# MiniMixer.net
KiCad netlist of a schematic drawn in EAGLE
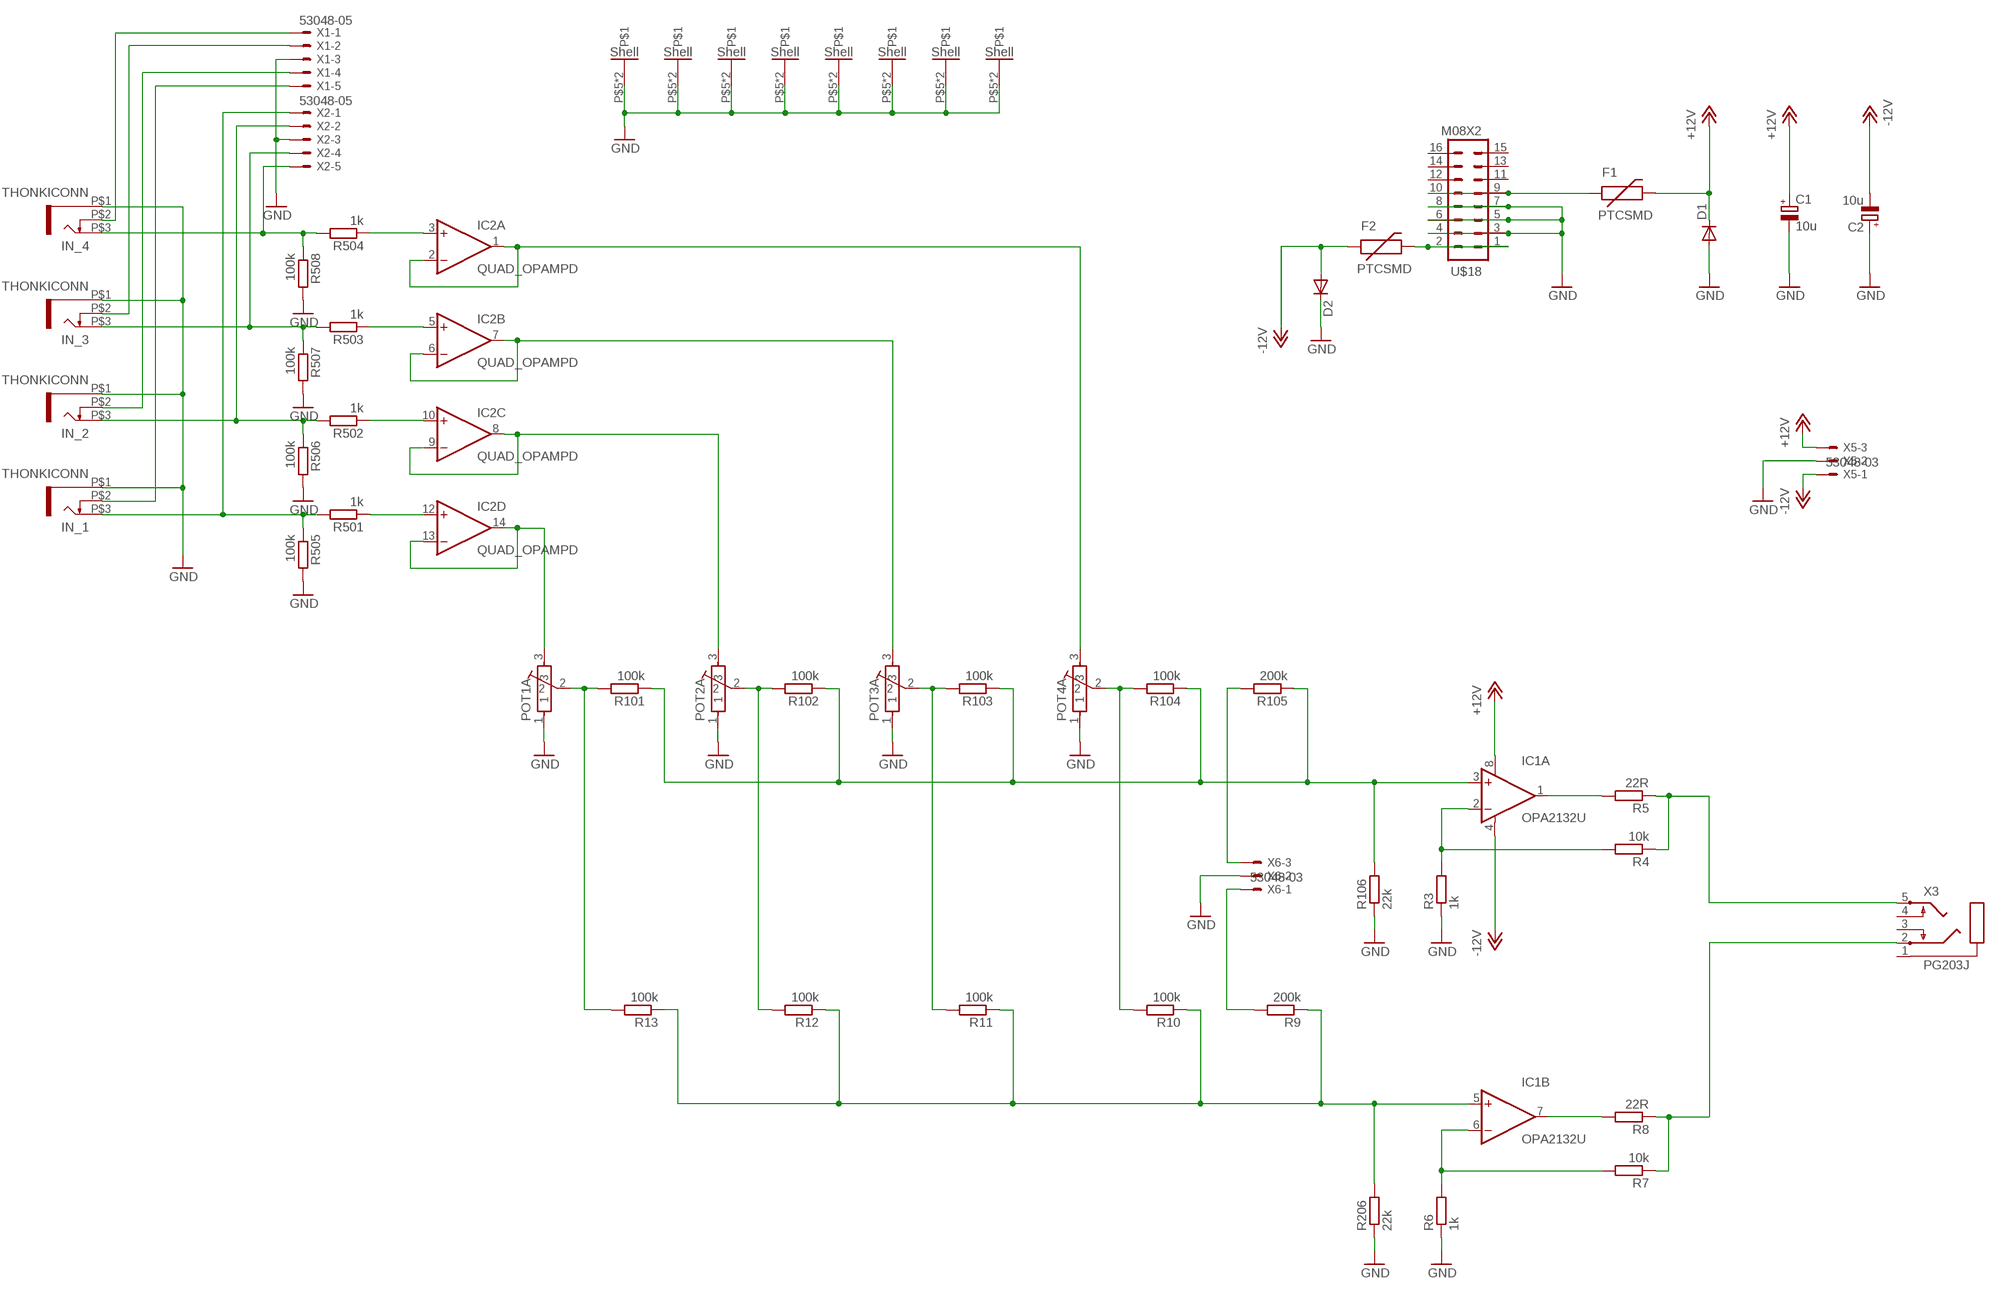
[diagram p0: schematic, sheet 1]

(export (version "E")
  (design (tool "Eeschema 10.0.6"))
  (components
    (comp (ref "C1")
      (value "10u")
      (footprint "eagle-import:153CLV-0505")
      (libsource (lib "eagle-import") (part "CPOL-EU153CLV-0505"))
    )
    (comp (ref "C2")
      (value "10u")
      (footprint "eagle-import:153CLV-0505")
      (libsource (lib "eagle-import") (part "CPOL-EU153CLV-0505"))
    )
    (comp (ref "D1")
      (value "DIODESMA")
      (footprint "eagle-import:SMA-DIODE")
      (libsource (lib "eagle-import") (part "DIODESMA"))
    )
    (comp (ref "D2")
      (value "DIODESMA")
      (footprint "eagle-import:SMA-DIODE")
      (libsource (lib "eagle-import") (part "DIODESMA"))
    )
    (comp (ref "F1")
      (value "PTCSMD")
      (footprint "eagle-import:PTC-1206")
      (libsource (lib "eagle-import") (part "PTCSMD"))
    )
    (comp (ref "F2")
      (value "PTCSMD")
      (footprint "eagle-import:PTC-1206")
      (libsource (lib "eagle-import") (part "PTCSMD"))
    )
    (comp (ref "IC1")
      (value "OPA2132U")
      (footprint "eagle-import:SO08")
      (fields (field (name "MF") "TEXAS INSTRUMENTS"))
      (libsource (lib "eagle-import") (part "OPA2132U"))
    )
    (comp (ref "IC2")
      (value "QUAD_OPAMPD")
      (footprint "eagle-import:SO14")
      (libsource (lib "eagle-import") (part "QUAD_OPAMPD"))
    )
    (comp (ref "IN_1")
      (value "THONKICONN")
      (footprint "eagle-import:THONKICONN")
      (libsource (lib "eagle-import") (part "THONKICONN"))
    )
    (comp (ref "IN_2")
      (value "THONKICONN")
      (footprint "eagle-import:THONKICONN")
      (libsource (lib "eagle-import") (part "THONKICONN"))
    )
    (comp (ref "IN_3")
      (value "THONKICONN")
      (footprint "eagle-import:THONKICONN")
      (libsource (lib "eagle-import") (part "THONKICONN"))
    )
    (comp (ref "IN_4")
      (value "THONKICONN")
      (footprint "eagle-import:THONKICONN")
      (libsource (lib "eagle-import") (part "THONKICONN"))
    )
    (comp (ref "POT1A")
      (value "POT-ALPS-RK09L1140")
      (footprint "eagle-import:POT-ALPS-RK09L1140")
      (libsource (lib "eagle-import") (part "POT-ALPS-RK09L1140"))
    )
    (comp (ref "POT1B")
      (value "POT-ALPS-RK09L1140")
      (footprint "eagle-import:POT-ALPS-RK09L1140")
      (libsource (lib "eagle-import") (part "POT-ALPS-RK09L1140"))
    )
    (comp (ref "POT2A")
      (value "POT-ALPS-RK09L1140")
      (footprint "eagle-import:POT-ALPS-RK09L1140")
      (libsource (lib "eagle-import") (part "POT-ALPS-RK09L1140"))
    )
    (comp (ref "POT2B")
      (value "POT-ALPS-RK09L1140")
      (footprint "eagle-import:POT-ALPS-RK09L1140")
      (libsource (lib "eagle-import") (part "POT-ALPS-RK09L1140"))
    )
    (comp (ref "POT3A")
      (value "POT-ALPS-RK09L1140")
      (footprint "eagle-import:POT-ALPS-RK09L1140")
      (libsource (lib "eagle-import") (part "POT-ALPS-RK09L1140"))
    )
    (comp (ref "POT3B")
      (value "POT-ALPS-RK09L1140")
      (footprint "eagle-import:POT-ALPS-RK09L1140")
      (libsource (lib "eagle-import") (part "POT-ALPS-RK09L1140"))
    )
    (comp (ref "POT4A")
      (value "POT-ALPS-RK09L1140")
      (footprint "eagle-import:POT-ALPS-RK09L1140")
      (libsource (lib "eagle-import") (part "POT-ALPS-RK09L1140"))
    )
    (comp (ref "POT4B")
      (value "POT-ALPS-RK09L1140")
      (footprint "eagle-import:POT-ALPS-RK09L1140")
      (libsource (lib "eagle-import") (part "POT-ALPS-RK09L1140"))
    )
    (comp (ref "R3")
      (value "1k")
      (footprint "eagle-import:0603")
      (libsource (lib "eagle-import") (part "R-EU_0603"))
    )
    (comp (ref "R4")
      (value "10k")
      (footprint "eagle-import:0603")
      (libsource (lib "eagle-import") (part "R-EU_0603"))
    )
    (comp (ref "R5")
      (value "22R")
      (footprint "eagle-import:0603")
      (libsource (lib "eagle-import") (part "R-EU_0603"))
    )
    (comp (ref "R6")
      (value "1k")
      (footprint "eagle-import:0603")
      (libsource (lib "eagle-import") (part "R-EU_0603"))
    )
    (comp (ref "R7")
      (value "10k")
      (footprint "eagle-import:0603")
      (libsource (lib "eagle-import") (part "R-EU_0603"))
    )
    (comp (ref "R8")
      (value "22R")
      (footprint "eagle-import:0603")
      (libsource (lib "eagle-import") (part "R-EU_0603"))
    )
    (comp (ref "R9")
      (value "200k")
      (footprint "eagle-import:R0603")
      (libsource (lib "eagle-import") (part "R-EU_R0603"))
    )
    (comp (ref "R10")
      (value "100k")
      (footprint "eagle-import:R0603")
      (libsource (lib "eagle-import") (part "R-EU_R0603"))
    )
    (comp (ref "R11")
      (value "100k")
      (footprint "eagle-import:R0603")
      (libsource (lib "eagle-import") (part "R-EU_R0603"))
    )
    (comp (ref "R12")
      (value "100k")
      (footprint "eagle-import:R0603")
      (libsource (lib "eagle-import") (part "R-EU_R0603"))
    )
    (comp (ref "R13")
      (value "100k")
      (footprint "eagle-import:R0603")
      (libsource (lib "eagle-import") (part "R-EU_R0603"))
    )
    (comp (ref "R101")
      (value "100k")
      (footprint "eagle-import:R0603")
      (libsource (lib "eagle-import") (part "R-EU_R0603"))
    )
    (comp (ref "R102")
      (value "100k")
      (footprint "eagle-import:R0603")
      (libsource (lib "eagle-import") (part "R-EU_R0603"))
    )
    (comp (ref "R103")
      (value "100k")
      (footprint "eagle-import:R0603")
      (libsource (lib "eagle-import") (part "R-EU_R0603"))
    )
    (comp (ref "R104")
      (value "100k")
      (footprint "eagle-import:R0603")
      (libsource (lib "eagle-import") (part "R-EU_R0603"))
    )
    (comp (ref "R105")
      (value "200k")
      (footprint "eagle-import:R0603")
      (libsource (lib "eagle-import") (part "R-EU_R0603"))
    )
    (comp (ref "R106")
      (value "22k")
      (footprint "eagle-import:0603")
      (libsource (lib "eagle-import") (part "R-EU_0603"))
    )
    (comp (ref "R206")
      (value "22k")
      (footprint "eagle-import:0603")
      (libsource (lib "eagle-import") (part "R-EU_0603"))
    )
    (comp (ref "R501")
      (value "1k")
      (footprint "eagle-import:R0603")
      (libsource (lib "eagle-import") (part "R-EU_R0603"))
    )
    (comp (ref "R502")
      (value "1k")
      (footprint "eagle-import:R0603")
      (libsource (lib "eagle-import") (part "R-EU_R0603"))
    )
    (comp (ref "R503")
      (value "1k")
      (footprint "eagle-import:R0603")
      (libsource (lib "eagle-import") (part "R-EU_R0603"))
    )
    (comp (ref "R504")
      (value "1k")
      (footprint "eagle-import:R0603")
      (libsource (lib "eagle-import") (part "R-EU_R0603"))
    )
    (comp (ref "R505")
      (value "100k")
      (footprint "eagle-import:R0603")
      (libsource (lib "eagle-import") (part "R-EU_R0603"))
    )
    (comp (ref "R506")
      (value "100k")
      (footprint "eagle-import:R0603")
      (libsource (lib "eagle-import") (part "R-EU_R0603"))
    )
    (comp (ref "R507")
      (value "100k")
      (footprint "eagle-import:R0603")
      (libsource (lib "eagle-import") (part "R-EU_R0603"))
    )
    (comp (ref "R508")
      (value "100k")
      (footprint "eagle-import:R0603")
      (libsource (lib "eagle-import") (part "R-EU_R0603"))
    )
    (comp (ref "U$18")
      (value "M08X2")
      (footprint "eagle-import:2X8")
      (libsource (lib "eagle-import") (part "M08X2"))
    )
    (comp (ref "X1")
      (value "53048-05")
      (footprint "eagle-import:53048-05")
      (fields (field (name "MF") "MOLEX") (field (name "MPN") "53048-0510"))
      (libsource (lib "eagle-import") (part "53?-05048"))
    )
    (comp (ref "X2")
      (value "53048-05")
      (footprint "eagle-import:53048-05")
      (fields (field (name "MF") "MOLEX") (field (name "MPN") "53048-0510"))
      (libsource (lib "eagle-import") (part "53?-05048"))
    )
    (comp (ref "X3")
      (value "PG203J")
      (footprint "eagle-import:PG203J")
      (libsource (lib "eagle-import") (part "PG203J"))
    )
    (comp (ref "X5")
      (value "53048-03")
      (footprint "eagle-import:53048-03")
      (fields (field (name "MF") "WALDOM/MOLEX") (field (name "MPN") "53048-0310"))
      (libsource (lib "eagle-import") (part "53?-03048"))
    )
    (comp (ref "X6")
      (value "53048-03")
      (footprint "eagle-import:53048-03")
      (fields (field (name "MF") "WALDOM/MOLEX") (field (name "MPN") "53048-0310"))
      (libsource (lib "eagle-import") (part "53?-03048"))
    )
  )
  (nets
    (net (code "1") (name "+12V") (class "Default")
      (node (ref "C1") (pin "+") (pinfunction "+_+") (pintype "passive"))
      (node (ref "D1") (pin "C") (pinfunction "C_C") (pintype "passive"))
      (node (ref "F1") (pin "2") (pinfunction "2_2") (pintype "bidirectional"))
      (node (ref "IC1") (pin "8") (pinfunction "V+_8") (pintype "power_in"))
      (node (ref "X5") (pin "3") (pinfunction "S_3") (pintype "passive"))
    )
    (net (code "2") (name "-12V") (class "Default")
      (node (ref "C2") (pin "-") (pinfunction "-_-") (pintype "passive"))
      (node (ref "D2") (pin "A") (pinfunction "A_A") (pintype "passive"))
      (node (ref "F2") (pin "1") (pinfunction "1_1") (pintype "bidirectional"))
      (node (ref "IC1") (pin "4") (pinfunction "V-_4") (pintype "power_in"))
      (node (ref "X5") (pin "1") (pinfunction "S_1") (pintype "passive"))
    )
    (net (code "3") (name "GND") (class "Default")
      (node (ref "C1") (pin "-") (pinfunction "-_-") (pintype "passive"))
      (node (ref "C2") (pin "+") (pinfunction "+_+") (pintype "passive"))
      (node (ref "D1") (pin "A") (pinfunction "A_A") (pintype "passive"))
      (node (ref "D2") (pin "C") (pinfunction "C_C") (pintype "passive"))
      (node (ref "IN_1") (pin "P$1") (pinfunction "5_P$1") (pintype "passive"))
      (node (ref "IN_2") (pin "P$1") (pinfunction "5_P$1") (pintype "passive"))
      (node (ref "IN_3") (pin "P$1") (pinfunction "5_P$1") (pintype "passive"))
      (node (ref "IN_4") (pin "P$1") (pinfunction "5_P$1") (pintype "passive"))
      (node (ref "POT1A") (pin "1") (pinfunction "1_1") (pintype "bidirectional"))
      (node (ref "POT1A") (pin "P$5") (pinfunction "P$1_P$5") (pintype "bidirectional"))
      (node (ref "POT1A") (pin "P$6") (pinfunction "P$1_P$6") (pintype "bidirectional"))
      (node (ref "POT1B") (pin "P$5") (pinfunction "P$1_P$5") (pintype "bidirectional"))
      (node (ref "POT1B") (pin "P$6") (pinfunction "P$1_P$6") (pintype "bidirectional"))
      (node (ref "POT2A") (pin "1") (pinfunction "1_1") (pintype "bidirectional"))
      (node (ref "POT2A") (pin "P$5") (pinfunction "P$1_P$5") (pintype "bidirectional"))
      (node (ref "POT2A") (pin "P$6") (pinfunction "P$1_P$6") (pintype "bidirectional"))
      (node (ref "POT2B") (pin "P$5") (pinfunction "P$1_P$5") (pintype "bidirectional"))
      (node (ref "POT2B") (pin "P$6") (pinfunction "P$1_P$6") (pintype "bidirectional"))
      (node (ref "POT3A") (pin "1") (pinfunction "1_1") (pintype "bidirectional"))
      (node (ref "POT3A") (pin "P$5") (pinfunction "P$1_P$5") (pintype "bidirectional"))
      (node (ref "POT3A") (pin "P$6") (pinfunction "P$1_P$6") (pintype "bidirectional"))
      (node (ref "POT3B") (pin "P$5") (pinfunction "P$1_P$5") (pintype "bidirectional"))
      (node (ref "POT3B") (pin "P$6") (pinfunction "P$1_P$6") (pintype "bidirectional"))
      (node (ref "POT4A") (pin "1") (pinfunction "1_1") (pintype "bidirectional"))
      (node (ref "POT4A") (pin "P$5") (pinfunction "P$1_P$5") (pintype "bidirectional"))
      (node (ref "POT4A") (pin "P$6") (pinfunction "P$1_P$6") (pintype "bidirectional"))
      (node (ref "POT4B") (pin "P$5") (pinfunction "P$1_P$5") (pintype "bidirectional"))
      (node (ref "POT4B") (pin "P$6") (pinfunction "P$1_P$6") (pintype "bidirectional"))
      (node (ref "R106") (pin "1") (pinfunction "1_1") (pintype "passive"))
      (node (ref "R206") (pin "1") (pinfunction "1_1") (pintype "passive"))
      (node (ref "R3") (pin "1") (pinfunction "1_1") (pintype "passive"))
      (node (ref "R505") (pin "2") (pinfunction "2_2") (pintype "passive"))
      (node (ref "R506") (pin "2") (pinfunction "2_2") (pintype "passive"))
      (node (ref "R507") (pin "2") (pinfunction "2_2") (pintype "passive"))
      (node (ref "R508") (pin "2") (pinfunction "2_2") (pintype "passive"))
      (node (ref "R6") (pin "1") (pinfunction "1_1") (pintype "passive"))
      (node (ref "U$18") (pin "3") (pinfunction "3_3") (pintype "passive"))
      (node (ref "U$18") (pin "4") (pinfunction "4_4") (pintype "passive"))
      (node (ref "U$18") (pin "5") (pinfunction "5_5") (pintype "passive"))
      (node (ref "U$18") (pin "6") (pinfunction "6_6") (pintype "passive"))
      (node (ref "U$18") (pin "7") (pinfunction "7_7") (pintype "passive"))
      (node (ref "U$18") (pin "8") (pinfunction "8_8") (pintype "passive"))
      (node (ref "X1") (pin "3") (pinfunction "S_3") (pintype "passive"))
      (node (ref "X2") (pin "3") (pinfunction "S_3") (pintype "passive"))
      (node (ref "X5") (pin "2") (pinfunction "S_2") (pintype "passive"))
      (node (ref "X6") (pin "2") (pinfunction "S_2") (pintype "passive"))
    )
    (net (code "4") (name "Net-(F1-Pad1)") (class "Default")
      (node (ref "F1") (pin "1") (pinfunction "1_1") (pintype "bidirectional"))
      (node (ref "U$18") (pin "10") (pinfunction "10_10") (pintype "passive"))
      (node (ref "U$18") (pin "9") (pinfunction "9_9") (pintype "passive"))
    )
    (net (code "5") (name "Net-(F2-Pad2)") (class "Default")
      (node (ref "F2") (pin "2") (pinfunction "2_2") (pintype "bidirectional"))
      (node (ref "U$18") (pin "1") (pinfunction "1_1") (pintype "passive"))
      (node (ref "U$18") (pin "2") (pinfunction "2_2") (pintype "passive"))
    )
    (net (code "6") (name "Net-(IC1A-+IN)") (class "Default")
      (node (ref "IC1") (pin "3") (pinfunction "+IN_3") (pintype "input"))
      (node (ref "R101") (pin "1") (pinfunction "1_1") (pintype "passive"))
      (node (ref "R102") (pin "1") (pinfunction "1_1") (pintype "passive"))
      (node (ref "R103") (pin "1") (pinfunction "1_1") (pintype "passive"))
      (node (ref "R104") (pin "1") (pinfunction "1_1") (pintype "passive"))
      (node (ref "R105") (pin "1") (pinfunction "1_1") (pintype "passive"))
      (node (ref "R106") (pin "2") (pinfunction "2_2") (pintype "passive"))
    )
    (net (code "7") (name "Net-(IC1A--IN)") (class "Default")
      (node (ref "IC1") (pin "2") (pinfunction "-IN_2") (pintype "input"))
      (node (ref "R3") (pin "2") (pinfunction "2_2") (pintype "passive"))
      (node (ref "R4") (pin "2") (pinfunction "2_2") (pintype "passive"))
    )
    (net (code "8") (name "Net-(IC1A-OUT)") (class "Default")
      (node (ref "IC1") (pin "1") (pinfunction "OUT_1") (pintype "output"))
      (node (ref "R5") (pin "2") (pinfunction "2_2") (pintype "passive"))
    )
    (net (code "9") (name "Net-(IC1B-+IN)") (class "Default")
      (node (ref "IC1") (pin "5") (pinfunction "+IN_5") (pintype "input"))
      (node (ref "R10") (pin "1") (pinfunction "1_1") (pintype "passive"))
      (node (ref "R11") (pin "1") (pinfunction "1_1") (pintype "passive"))
      (node (ref "R12") (pin "1") (pinfunction "1_1") (pintype "passive"))
      (node (ref "R13") (pin "1") (pinfunction "1_1") (pintype "passive"))
      (node (ref "R206") (pin "2") (pinfunction "2_2") (pintype "passive"))
      (node (ref "R9") (pin "1") (pinfunction "1_1") (pintype "passive"))
    )
    (net (code "10") (name "Net-(IC1B--IN)") (class "Default")
      (node (ref "IC1") (pin "6") (pinfunction "-IN_6") (pintype "input"))
      (node (ref "R6") (pin "2") (pinfunction "2_2") (pintype "passive"))
      (node (ref "R7") (pin "2") (pinfunction "2_2") (pintype "passive"))
    )
    (net (code "11") (name "Net-(IC1B-OUT)") (class "Default")
      (node (ref "IC1") (pin "7") (pinfunction "OUT_7") (pintype "output"))
      (node (ref "R8") (pin "2") (pinfunction "2_2") (pintype "passive"))
    )
    (net (code "12") (name "Net-(IC2A-+IN)") (class "Default")
      (node (ref "IC2") (pin "3") (pinfunction "+IN_3") (pintype "input"))
      (node (ref "R504") (pin "1") (pinfunction "1_1") (pintype "passive"))
    )
    (net (code "13") (name "Net-(IC2A--IN)") (class "Default")
      (node (ref "IC2") (pin "1") (pinfunction "OUT_1") (pintype "output"))
      (node (ref "IC2") (pin "2") (pinfunction "-IN_2") (pintype "input"))
      (node (ref "POT4A") (pin "3") (pinfunction "3_3") (pintype "bidirectional"))
    )
    (net (code "14") (name "Net-(IC2B-+IN)") (class "Default")
      (node (ref "IC2") (pin "5") (pinfunction "+IN_5") (pintype "input"))
      (node (ref "R503") (pin "1") (pinfunction "1_1") (pintype "passive"))
    )
    (net (code "15") (name "Net-(IC2B--IN)") (class "Default")
      (node (ref "IC2") (pin "6") (pinfunction "-IN_6") (pintype "input"))
      (node (ref "IC2") (pin "7") (pinfunction "OUT_7") (pintype "output"))
      (node (ref "POT3A") (pin "3") (pinfunction "3_3") (pintype "bidirectional"))
    )
    (net (code "16") (name "Net-(IC2C-+IN)") (class "Default")
      (node (ref "IC2") (pin "10") (pinfunction "+IN_10") (pintype "input"))
      (node (ref "R502") (pin "1") (pinfunction "1_1") (pintype "passive"))
    )
    (net (code "17") (name "Net-(IC2C--IN)") (class "Default")
      (node (ref "IC2") (pin "8") (pinfunction "OUT_8") (pintype "output"))
      (node (ref "IC2") (pin "9") (pinfunction "-IN_9") (pintype "input"))
      (node (ref "POT2A") (pin "3") (pinfunction "3_3") (pintype "bidirectional"))
    )
    (net (code "18") (name "Net-(IC2D-+IN)") (class "Default")
      (node (ref "IC2") (pin "12") (pinfunction "+IN_12") (pintype "input"))
      (node (ref "R501") (pin "1") (pinfunction "1_1") (pintype "passive"))
    )
    (net (code "19") (name "Net-(IC2D--IN)") (class "Default")
      (node (ref "IC2") (pin "13") (pinfunction "-IN_13") (pintype "input"))
      (node (ref "IC2") (pin "14") (pinfunction "OUT_14") (pintype "output"))
      (node (ref "POT1A") (pin "3") (pinfunction "3_3") (pintype "bidirectional"))
    )
    (net (code "20") (name "Net-(IN_1-3)") (class "Default")
      (node (ref "IN_1") (pin "P$3") (pinfunction "3_P$3") (pintype "passive"))
      (node (ref "R501") (pin "2") (pinfunction "2_2") (pintype "passive"))
      (node (ref "R505") (pin "1") (pinfunction "1_1") (pintype "passive"))
      (node (ref "X2") (pin "1") (pinfunction "S_1") (pintype "passive"))
    )
    (net (code "21") (name "Net-(IN_1-4)") (class "Default")
      (node (ref "IN_1") (pin "P$2") (pinfunction "4_P$2") (pintype "passive"))
      (node (ref "X1") (pin "5") (pinfunction "S_5") (pintype "passive"))
    )
    (net (code "22") (name "Net-(IN_2-3)") (class "Default")
      (node (ref "IN_2") (pin "P$3") (pinfunction "3_P$3") (pintype "passive"))
      (node (ref "R502") (pin "2") (pinfunction "2_2") (pintype "passive"))
      (node (ref "R506") (pin "1") (pinfunction "1_1") (pintype "passive"))
      (node (ref "X2") (pin "2") (pinfunction "S_2") (pintype "passive"))
    )
    (net (code "23") (name "Net-(IN_2-4)") (class "Default")
      (node (ref "IN_2") (pin "P$2") (pinfunction "4_P$2") (pintype "passive"))
      (node (ref "X1") (pin "4") (pinfunction "S_4") (pintype "passive"))
    )
    (net (code "24") (name "Net-(IN_3-3)") (class "Default")
      (node (ref "IN_3") (pin "P$3") (pinfunction "3_P$3") (pintype "passive"))
      (node (ref "R503") (pin "2") (pinfunction "2_2") (pintype "passive"))
      (node (ref "R507") (pin "1") (pinfunction "1_1") (pintype "passive"))
      (node (ref "X2") (pin "4") (pinfunction "S_4") (pintype "passive"))
    )
    (net (code "25") (name "Net-(IN_3-4)") (class "Default")
      (node (ref "IN_3") (pin "P$2") (pinfunction "4_P$2") (pintype "passive"))
      (node (ref "X1") (pin "2") (pinfunction "S_2") (pintype "passive"))
    )
    (net (code "26") (name "Net-(IN_4-3)") (class "Default")
      (node (ref "IN_4") (pin "P$3") (pinfunction "3_P$3") (pintype "passive"))
      (node (ref "R504") (pin "2") (pinfunction "2_2") (pintype "passive"))
      (node (ref "R508") (pin "1") (pinfunction "1_1") (pintype "passive"))
      (node (ref "X2") (pin "5") (pinfunction "S_5") (pintype "passive"))
    )
    (net (code "27") (name "Net-(IN_4-4)") (class "Default")
      (node (ref "IN_4") (pin "P$2") (pinfunction "4_P$2") (pintype "passive"))
      (node (ref "X1") (pin "1") (pinfunction "S_1") (pintype "passive"))
    )
    (net (code "28") (name "Net-(POT1A-Pad2)") (class "Default")
      (node (ref "POT1A") (pin "2") (pinfunction "2_2") (pintype "bidirectional"))
      (node (ref "R101") (pin "2") (pinfunction "2_2") (pintype "passive"))
      (node (ref "R13") (pin "2") (pinfunction "2_2") (pintype "passive"))
    )
    (net (code "29") (name "Net-(POT2A-Pad2)") (class "Default")
      (node (ref "POT2A") (pin "2") (pinfunction "2_2") (pintype "bidirectional"))
      (node (ref "R102") (pin "2") (pinfunction "2_2") (pintype "passive"))
      (node (ref "R12") (pin "2") (pinfunction "2_2") (pintype "passive"))
    )
    (net (code "30") (name "Net-(POT3A-Pad2)") (class "Default")
      (node (ref "POT3A") (pin "2") (pinfunction "2_2") (pintype "bidirectional"))
      (node (ref "R103") (pin "2") (pinfunction "2_2") (pintype "passive"))
      (node (ref "R11") (pin "2") (pinfunction "2_2") (pintype "passive"))
    )
    (net (code "31") (name "Net-(POT4A-Pad2)") (class "Default")
      (node (ref "POT4A") (pin "2") (pinfunction "2_2") (pintype "bidirectional"))
      (node (ref "R10") (pin "2") (pinfunction "2_2") (pintype "passive"))
      (node (ref "R104") (pin "2") (pinfunction "2_2") (pintype "passive"))
    )
    (net (code "32") (name "Net-(R4-Pad1)") (class "Default")
      (node (ref "R4") (pin "1") (pinfunction "1_1") (pintype "passive"))
      (node (ref "R5") (pin "1") (pinfunction "1_1") (pintype "passive"))
      (node (ref "X3") (pin "5") (pinfunction "5_5") (pintype "passive"))
    )
    (net (code "33") (name "Net-(R7-Pad1)") (class "Default")
      (node (ref "R7") (pin "1") (pinfunction "1_1") (pintype "passive"))
      (node (ref "R8") (pin "1") (pinfunction "1_1") (pintype "passive"))
      (node (ref "X3") (pin "2") (pinfunction "2_2") (pintype "passive"))
    )
    (net (code "34") (name "Net-(X6A-S)") (class "Default")
      (node (ref "R9") (pin "2") (pinfunction "2_2") (pintype "passive"))
      (node (ref "X6") (pin "1") (pinfunction "S_1") (pintype "passive"))
    )
    (net (code "35") (name "Net-(X6C-S)") (class "Default")
      (node (ref "R105") (pin "2") (pinfunction "2_2") (pintype "passive"))
      (node (ref "X6") (pin "3") (pinfunction "S_3") (pintype "passive"))
    )
    (net (code "36") (name "unconnected-(U$18-Pad11)") (class "Default")
      (node (ref "U$18") (pin "11") (pinfunction "11_11") (pintype "passive"))
    )
    (net (code "37") (name "unconnected-(U$18-Pad12)") (class "Default")
      (node (ref "U$18") (pin "12") (pinfunction "12_12") (pintype "passive"))
    )
    (net (code "38") (name "unconnected-(U$18-Pad13)") (class "Default")
      (node (ref "U$18") (pin "13") (pinfunction "13_13") (pintype "passive"))
    )
    (net (code "39") (name "unconnected-(U$18-Pad14)") (class "Default")
      (node (ref "U$18") (pin "14") (pinfunction "14_14") (pintype "passive"))
    )
    (net (code "40") (name "unconnected-(U$18-Pad15)") (class "Default")
      (node (ref "U$18") (pin "15") (pinfunction "15_15") (pintype "passive"))
    )
    (net (code "41") (name "unconnected-(U$18-Pad16)") (class "Default")
      (node (ref "U$18") (pin "16") (pinfunction "16_16") (pintype "passive"))
    )
    (net (code "42") (name "unconnected-(X3-Pad1)") (class "Default")
      (node (ref "X3") (pin "1") (pinfunction "1_1") (pintype "passive"))
    )
    (net (code "43") (name "unconnected-(X3-Pad3)") (class "Default")
      (node (ref "X3") (pin "3") (pinfunction "3_3") (pintype "passive"))
    )
    (net (code "44") (name "unconnected-(X3-Pad4)") (class "Default")
      (node (ref "X3") (pin "4") (pinfunction "4_4") (pintype "passive"))
    )
  )
)
